# GuitarPreamp1.net
KiCad netlist of a schematic drawn in Altium Designer
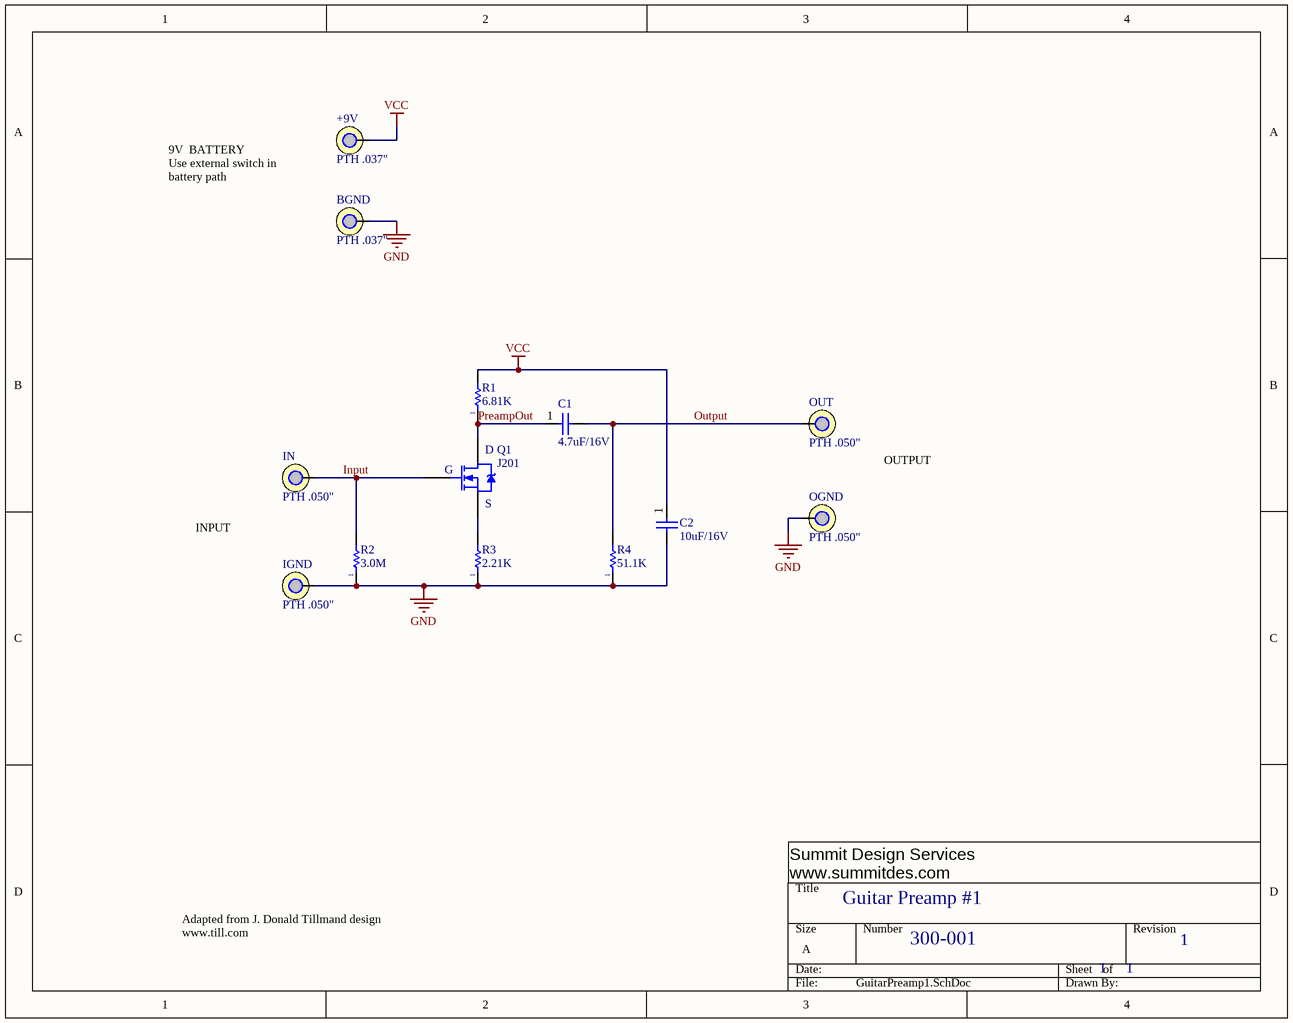
[diagram p0: GuitarPreamp1.SchDoc]

(export (version "E")
  (design (tool "Eeschema 10.0.6"))
  (components
    (comp (ref "+9V")
      (value "~")
      (footprint "PTH_037")
      (description "PTH .037\"")
      (fields (field (name "DISPLAY VALUE") "PTH .037\"") (field (name "PART NUMBER") "250-002"))
      (libsource (lib "") (part "PTH_1"))
    )
    (comp (ref "BGND")
      (value "~")
      (footprint "PTH_037")
      (description "PTH .037\"")
      (fields (field (name "DISPLAY VALUE") "PTH .037\"") (field (name "PART NUMBER") "250-002"))
      (libsource (lib "") (part "PTH_1"))
    )
    (comp (ref "C1")
      (value "~")
      (footprint "0805C")
      (description "4.7UF 16V Y5V 0805")
      (fields
        (field (name "DISPLAY VALUE") "4.7uF/16V")
        (field (name "PART NUMBER") "200-003")
        (field (name "MANUFACTURER") "TDK")
      )
      (libsource (lib "SDS_Parts") (part "CAP_NP"))
    )
    (comp (ref "C2")
      (value "~")
      (footprint "1206C")
      (description "10UF 16V Y5V 1206")
      (fields
        (field (name "DISPLAY VALUE") "10uF/16V")
        (field (name "PART NUMBER") "200-002")
        (field (name "MANUFACTURER") "Murata")
      )
      (libsource (lib "SDS_Parts") (part "CAP_NP"))
    )
    (comp (ref "IGND")
      (value "~")
      (footprint "PTH_050")
      (description "PTH .050\"")
      (fields (field (name "DISPLAY VALUE") "PTH .050\"") (field (name "PART NUMBER") "250-003"))
      (libsource (lib "") (part "PTH_1"))
    )
    (comp (ref "IN")
      (value "~")
      (footprint "PTH_050")
      (description "PTH .050\"")
      (fields (field (name "DISPLAY VALUE") "PTH .050\"") (field (name "PART NUMBER") "250-003"))
      (libsource (lib "") (part "PTH_1"))
    )
    (comp (ref "OGND")
      (value "~")
      (footprint "PTH_050")
      (description "PTH .050\"")
      (fields (field (name "DISPLAY VALUE") "PTH .050\"") (field (name "PART NUMBER") "250-003"))
      (libsource (lib "SDS_Parts") (part "PTH"))
    )
    (comp (ref "OUT")
      (value "~")
      (footprint "PTH_050")
      (description "PTH .050\"")
      (fields (field (name "DISPLAY VALUE") "PTH .050\"") (field (name "PART NUMBER") "250-003"))
      (libsource (lib "SDS_Parts") (part "PTH"))
    )
    (comp (ref "Q1")
      (value "~")
      (footprint "SOT23-3-A")
      (description "IC SWITCH N-CH 40V 50MA SOT-23")
      (fields
        (field (name "MANUFACTURER") "Fairchild")
        (field (name "DISPLAY VALUE") "J201")
        (field (name "PART NUMBER") "230-001")
      )
      (libsource (lib "SDS_Parts") (part "NFET"))
    )
    (comp (ref "R1")
      (value "~")
      (footprint "0805R")
      (description "RES 6.81K OHM 1/8W 1% 0805")
      (fields
        (field (name "DISPLAY VALUE") "6.81K")
        (field (name "PART NUMBER") "210-002")
        (field (name "MANUFACTURER") "Panasonic")
      )
      (libsource (lib "SDS_Parts") (part "RES"))
    )
    (comp (ref "R2")
      (value "~")
      (footprint "0805R")
      (description "RES 3.0M OHM 1/8W 5% 0805")
      (fields
        (field (name "DISPLAY VALUE") "3.0M")
        (field (name "PART NUMBER") "210-005")
        (field (name "MANUFACTURER") "Panasonic")
      )
      (libsource (lib "SDS_Parts") (part "RES"))
    )
    (comp (ref "R3")
      (value "~")
      (footprint "0805R")
      (description "RES 2.21K OHM 1/8W 1% 0805")
      (fields
        (field (name "DISPLAY VALUE") "2.21K")
        (field (name "PART NUMBER") "210-003")
        (field (name "MANUFACTURER") "Panasonic")
      )
      (libsource (lib "SDS_Parts") (part "RES"))
    )
    (comp (ref "R4")
      (value "~")
      (footprint "0805R")
      (description "RES 51.1K OHM 1/8W 1% 0805")
      (fields
        (field (name "DISPLAY VALUE") "51.1K")
        (field (name "PART NUMBER") "210-004")
        (field (name "MANUFACTURER") "Panasonic")
      )
      (libsource (lib "SDS_Parts") (part "RES"))
    )
  )
  (nets
    (net (code "1") (name "/Input") (class "Default")
      (node (ref "IN") (pin "1") (pinfunction "1_1") (pintype "passive"))
      (node (ref "Q1") (pin "G") (pinfunction "G_G") (pintype "passive"))
      (node (ref "R2") (pin "2") (pinfunction "2_2") (pintype "passive"))
    )
    (net (code "2") (name "/Output") (class "Default")
      (node (ref "C1") (pin "2") (pinfunction "2_2") (pintype "passive"))
      (node (ref "OUT") (pin "1") (pinfunction "1_1") (pintype "passive"))
      (node (ref "R4") (pin "2") (pinfunction "2_2") (pintype "passive"))
    )
    (net (code "3") (name "/PreampOut") (class "Default")
      (node (ref "C1") (pin "1") (pinfunction "1_1") (pintype "passive"))
      (node (ref "Q1") (pin "D") (pinfunction "D_D") (pintype "passive"))
      (node (ref "R1") (pin "1") (pinfunction "1_1") (pintype "passive"))
    )
    (net (code "4") (name "GND") (class "Default")
      (node (ref "BGND") (pin "1") (pinfunction "1_1") (pintype "passive"))
      (node (ref "C2") (pin "2") (pinfunction "2_2") (pintype "passive"))
      (node (ref "IGND") (pin "1") (pinfunction "1_1") (pintype "passive"))
      (node (ref "OGND") (pin "1") (pinfunction "1_1") (pintype "passive"))
      (node (ref "R2") (pin "1") (pinfunction "1_1") (pintype "passive"))
      (node (ref "R3") (pin "1") (pinfunction "1_1") (pintype "passive"))
      (node (ref "R4") (pin "1") (pinfunction "1_1") (pintype "passive"))
    )
    (net (code "5") (name "Net-(Q1-PadS)") (class "Default")
      (node (ref "Q1") (pin "S") (pinfunction "S_S") (pintype "passive"))
      (node (ref "R3") (pin "2") (pinfunction "2_2") (pintype "passive"))
    )
    (net (code "6") (name "VCC") (class "Default")
      (node (ref "+9V") (pin "1") (pinfunction "1_1") (pintype "passive"))
      (node (ref "C2") (pin "1") (pinfunction "1_1") (pintype "passive"))
      (node (ref "R1") (pin "2") (pinfunction "2_2") (pintype "passive"))
    )
  )
)
